# SCH_power_long_clock_2022-06-03.net
KiCad netlist of a schematic drawn in EasyEDA
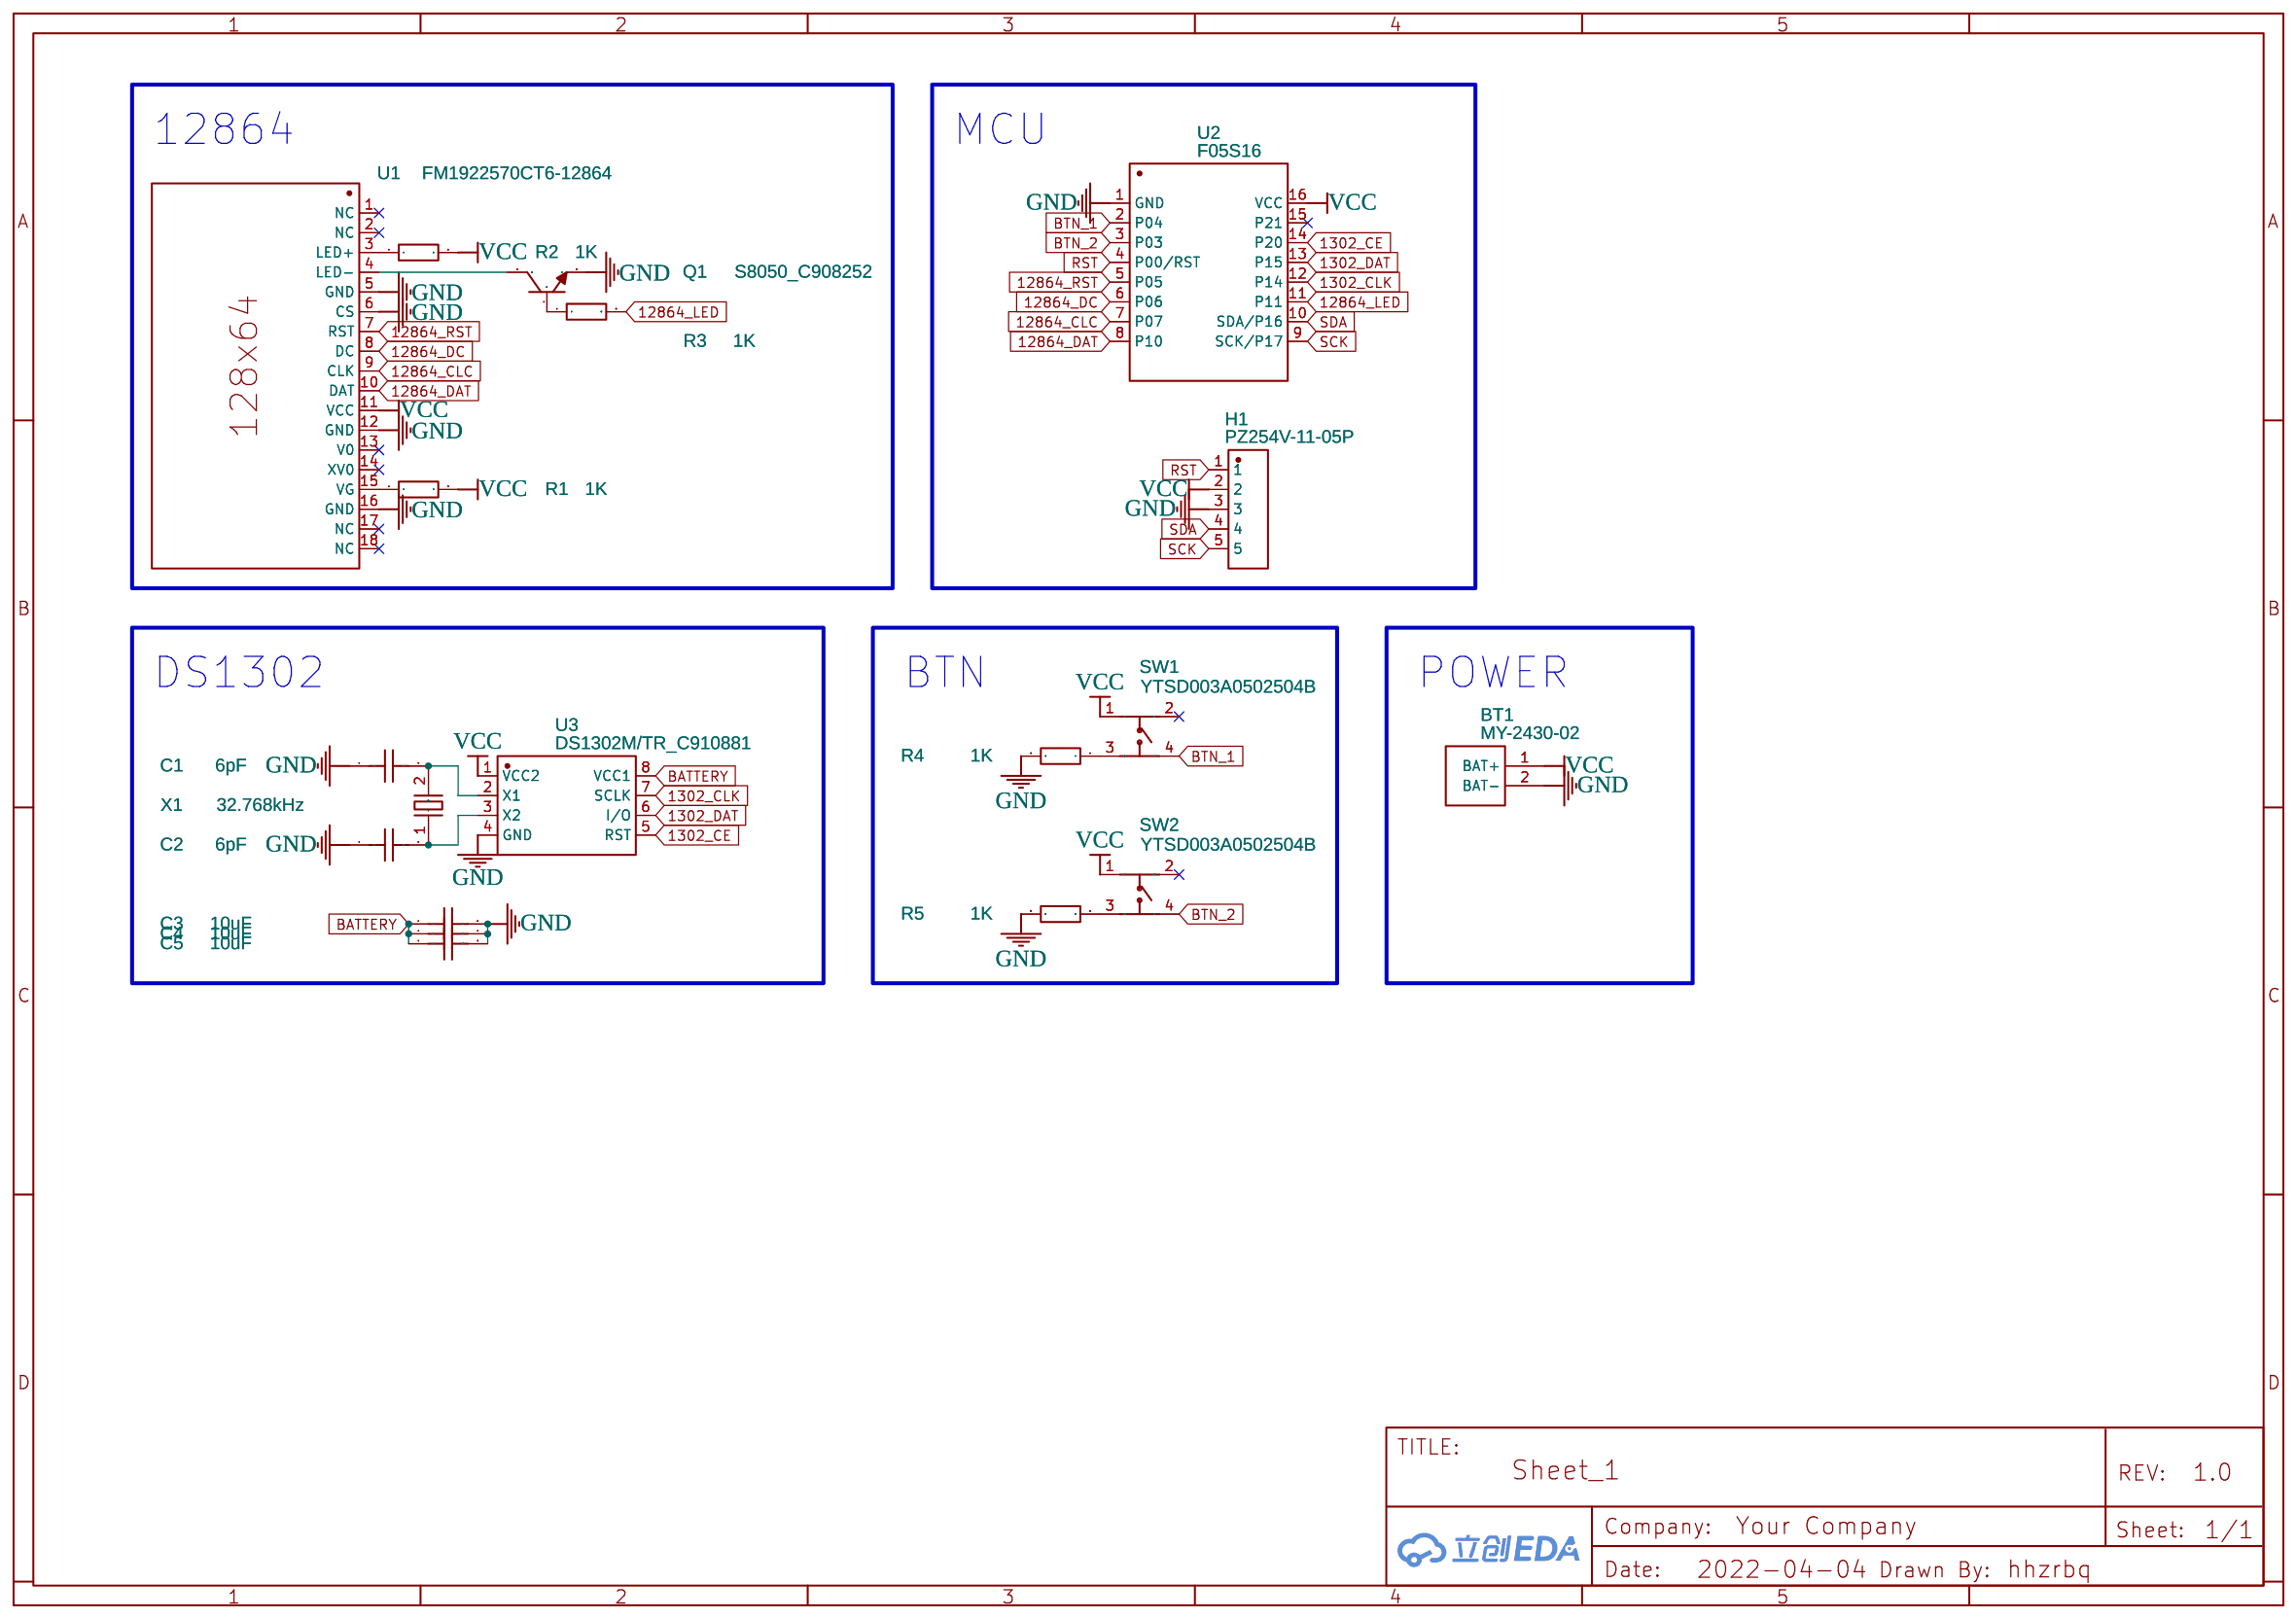
[diagram p0: schematic sheet]

(export (version "E")
  (design (tool "Eeschema 10.0.6"))
  (components
    (comp (ref "BT1")
      (value "MY-2430-02")
      (fields (field (name "BOM_Supplier Part") "C964843"))
      (libsource (lib "") (part "MY-2430-02"))
    )
    (comp (ref "C1")
      (value "6pF")
      (fields
        (field (name "BOM_Manufacturer Part") "0805N6R0D500CT")
        (field (name "BOM_Supplier Part") "C424859")
      )
      (libsource (lib "") (part "0805N6R0D500CT"))
    )
    (comp (ref "C2")
      (value "6pF")
      (fields
        (field (name "BOM_Manufacturer Part") "0805N6R0D500CT")
        (field (name "BOM_Supplier Part") "C424859")
      )
      (libsource (lib "") (part "0805N6R0D500CT"))
    )
    (comp (ref "C3") (value "10uF") (libsource (lib "") (part "C_0805_US")))
    (comp (ref "C4") (value "10uF") (libsource (lib "") (part "C_0805_US")))
    (comp (ref "C5") (value "10uF") (libsource (lib "") (part "C_0805_US")))
    (comp (ref "H1")
      (value "PZ254V-11-05P")
      (fields (field (name "BOM_Supplier Part") "C492404"))
      (libsource (lib "") (part "PZ254V-11-05P"))
    )
    (comp (ref "Q1")
      (value "S8050_C908252")
      (fields (field (name "BOM_Manufacturer Part") "S8050") (field (name "BOM_Supplier Part") "C908252"))
      (libsource (lib "") (part "S8050_C908252"))
    )
    (comp (ref "R1")
      (value "1K")
      (fields
        (field (name "BOM_Manufacturer Part") "RK73B2ATTD102J")
        (field (name "BOM_Supplier Part") "C159911")
      )
      (libsource (lib "") (part "RK73B2ATTD102J_1"))
    )
    (comp (ref "R2")
      (value "1K")
      (fields
        (field (name "BOM_Manufacturer Part") "RK73B2ATTD102J")
        (field (name "BOM_Supplier Part") "C159911")
      )
      (libsource (lib "") (part "RK73B2ATTD102J_1"))
    )
    (comp (ref "R3")
      (value "1K")
      (fields
        (field (name "BOM_Manufacturer Part") "RK73B2ATTD102J")
        (field (name "BOM_Supplier Part") "C159911")
      )
      (libsource (lib "") (part "RK73B2ATTD102J_1"))
    )
    (comp (ref "R4")
      (value "1K")
      (fields
        (field (name "BOM_Manufacturer Part") "RK73B2ATTD102J")
        (field (name "BOM_Supplier Part") "C159911")
      )
      (libsource (lib "") (part "RK73B2ATTD102J"))
    )
    (comp (ref "R5")
      (value "1K")
      (fields
        (field (name "BOM_Manufacturer Part") "RK73B2ATTD102J")
        (field (name "BOM_Supplier Part") "C159911")
      )
      (libsource (lib "") (part "RK73B2ATTD102J"))
    )
    (comp (ref "SW1")
      (value "YTSD003A0502504B")
      (fields (field (name "BOM_Supplier Part") "C2689406"))
      (libsource (lib "") (part "YTSD003A0502504B"))
    )
    (comp (ref "SW2")
      (value "YTSD003A0502504B")
      (fields (field (name "BOM_Supplier Part") "C2689406"))
      (libsource (lib "") (part "YTSD003A0502504B"))
    )
    (comp (ref "U1") (value "FM1922570CT6-12864") (libsource (lib "") (part "FM1922570CT6-12864")))
    (comp (ref "U2") (value "F05S16") (libsource (lib "") (part "F05S16")))
    (comp (ref "U3")
      (value "DS1302M/TR_C910881")
      (fields
        (field (name "BOM_Manufacturer Part") "DS1302M/TR")
        (field (name "BOM_Supplier Part") "C910881")
      )
      (libsource (lib "") (part "DS1302M/TR_C910881"))
    )
    (comp (ref "X1")
      (value "32.768kHz")
      (fields
        (field (name "BOM_Manufacturer Part") "Q13FC13500005")
        (field (name "BOM_Supplier Part") "C841881")
      )
      (libsource (lib "") (part "Q13FC13500005"))
    )
  )
  (nets
    (net (code "1") (name "1302_CE") (class "Default")
      (node (ref "U2") (pin "14") (pinfunction "P20_14") (pintype "bidirectional"))
      (node (ref "U3") (pin "5") (pinfunction "RST_5") (pintype "unspecified"))
    )
    (net (code "2") (name "1302_CLK") (class "Default")
      (node (ref "U2") (pin "12") (pinfunction "P14_12") (pintype "bidirectional"))
      (node (ref "U3") (pin "7") (pinfunction "SCLK_7") (pintype "unspecified"))
    )
    (net (code "3") (name "1302_DAT") (class "Default")
      (node (ref "U2") (pin "13") (pinfunction "P15_13") (pintype "bidirectional"))
      (node (ref "U3") (pin "6") (pinfunction "I/O_6") (pintype "unspecified"))
    )
    (net (code "4") (name "12864_CLC") (class "Default")
      (node (ref "U1") (pin "9") (pinfunction "CLK_9") (pintype "unspecified"))
      (node (ref "U2") (pin "7") (pinfunction "P07_7") (pintype "bidirectional"))
    )
    (net (code "5") (name "12864_DAT") (class "Default")
      (node (ref "U1") (pin "10") (pinfunction "DAT_10") (pintype "unspecified"))
      (node (ref "U2") (pin "8") (pinfunction "P10_8") (pintype "bidirectional"))
    )
    (net (code "6") (name "12864_DC") (class "Default")
      (node (ref "U1") (pin "8") (pinfunction "DC_8") (pintype "unspecified"))
      (node (ref "U2") (pin "6") (pinfunction "P06_6") (pintype "bidirectional"))
    )
    (net (code "7") (name "12864_LED") (class "Default")
      (node (ref "R3") (pin "2") (pinfunction "2_2") (pintype "unspecified"))
      (node (ref "U2") (pin "11") (pinfunction "P11_11") (pintype "bidirectional"))
    )
    (net (code "8") (name "12864_RST") (class "Default")
      (node (ref "U1") (pin "7") (pinfunction "RST_7") (pintype "unspecified"))
      (node (ref "U2") (pin "5") (pinfunction "P05_5") (pintype "bidirectional"))
    )
    (net (code "9") (name "BATTERY") (class "Default")
      (node (ref "C3") (pin "1") (pinfunction "1_1") (pintype "unspecified"))
      (node (ref "C4") (pin "1") (pinfunction "1_1") (pintype "unspecified"))
      (node (ref "C5") (pin "1") (pinfunction "1_1") (pintype "unspecified"))
      (node (ref "U3") (pin "8") (pinfunction "VCC1_8") (pintype "unspecified"))
    )
    (net (code "10") (name "BTN_1") (class "Default")
      (node (ref "SW1") (pin "4") (pinfunction "4_4") (pintype "unspecified"))
      (node (ref "U2") (pin "2") (pinfunction "P04_2") (pintype "bidirectional"))
    )
    (net (code "11") (name "BTN_2") (class "Default")
      (node (ref "SW2") (pin "4") (pinfunction "4_4") (pintype "unspecified"))
      (node (ref "U2") (pin "3") (pinfunction "P03_3") (pintype "bidirectional"))
    )
    (net (code "12") (name "GND") (class "Default")
      (node (ref "BT1") (pin "2") (pinfunction "BAT-_2") (pintype "unspecified"))
      (node (ref "C1") (pin "1") (pinfunction "1_1") (pintype "unspecified"))
      (node (ref "C2") (pin "1") (pinfunction "1_1") (pintype "unspecified"))
      (node (ref "C3") (pin "2") (pinfunction "2_2") (pintype "unspecified"))
      (node (ref "C4") (pin "2") (pinfunction "2_2") (pintype "unspecified"))
      (node (ref "C5") (pin "2") (pinfunction "2_2") (pintype "unspecified"))
      (node (ref "H1") (pin "3") (pinfunction "3_3") (pintype "unspecified"))
      (node (ref "Q1") (pin "2") (pinfunction "E_2") (pintype "input"))
      (node (ref "R4") (pin "2") (pinfunction "2_2") (pintype "unspecified"))
      (node (ref "R5") (pin "2") (pinfunction "2_2") (pintype "unspecified"))
      (node (ref "U1") (pin "12") (pinfunction "GND_12") (pintype "unspecified"))
      (node (ref "U1") (pin "16") (pinfunction "GND_16") (pintype "unspecified"))
      (node (ref "U1") (pin "5") (pinfunction "GND_5") (pintype "unspecified"))
      (node (ref "U1") (pin "6") (pinfunction "CS_6") (pintype "unspecified"))
      (node (ref "U2") (pin "1") (pinfunction "GND_1") (pintype "passive"))
      (node (ref "U3") (pin "4") (pinfunction "GND_4") (pintype "unspecified"))
    )
    (net (code "13") (name "Net-(Q1-B)") (class "Default")
      (node (ref "Q1") (pin "1") (pinfunction "B_1") (pintype "input"))
      (node (ref "R3") (pin "1") (pinfunction "1_1") (pintype "unspecified"))
    )
    (net (code "14") (name "Net-(Q1-C)") (class "Default")
      (node (ref "Q1") (pin "3") (pinfunction "C_3") (pintype "input"))
      (node (ref "U1") (pin "4") (pinfunction "LED-_4") (pintype "unspecified"))
    )
    (net (code "15") (name "Net-(R4-Pad1)") (class "Default")
      (node (ref "R4") (pin "1") (pinfunction "1_1") (pintype "unspecified"))
      (node (ref "SW1") (pin "3") (pinfunction "3_3") (pintype "unspecified"))
    )
    (net (code "16") (name "Net-(R5-Pad1)") (class "Default")
      (node (ref "R5") (pin "1") (pinfunction "1_1") (pintype "unspecified"))
      (node (ref "SW2") (pin "3") (pinfunction "3_3") (pintype "unspecified"))
    )
    (net (code "17") (name "Net-(U1-LED+)") (class "Default")
      (node (ref "R2") (pin "1") (pinfunction "1_1") (pintype "unspecified"))
      (node (ref "U1") (pin "3") (pinfunction "LED+_3") (pintype "unspecified"))
    )
    (net (code "18") (name "Net-(U1-VG)") (class "Default")
      (node (ref "R1") (pin "1") (pinfunction "1_1") (pintype "unspecified"))
      (node (ref "U1") (pin "15") (pinfunction "VG_15") (pintype "unspecified"))
    )
    (net (code "19") (name "Net-(U3-X1)") (class "Default")
      (node (ref "C1") (pin "2") (pinfunction "2_2") (pintype "unspecified"))
      (node (ref "U3") (pin "2") (pinfunction "X1_2") (pintype "unspecified"))
      (node (ref "X1") (pin "2") (pinfunction "GND_2") (pintype "input"))
    )
    (net (code "20") (name "Net-(U3-X2)") (class "Default")
      (node (ref "C2") (pin "2") (pinfunction "2_2") (pintype "unspecified"))
      (node (ref "U3") (pin "3") (pinfunction "X2_3") (pintype "unspecified"))
      (node (ref "X1") (pin "1") (pinfunction "1_1") (pintype "input"))
    )
    (net (code "21") (name "RST") (class "Default")
      (node (ref "H1") (pin "1") (pinfunction "1_1") (pintype "unspecified"))
      (node (ref "U2") (pin "4") (pinfunction "P00/RST_4") (pintype "bidirectional"))
    )
    (net (code "22") (name "SCK") (class "Default")
      (node (ref "H1") (pin "5") (pinfunction "5_5") (pintype "unspecified"))
      (node (ref "U2") (pin "9") (pinfunction "SCK/P17_9") (pintype "bidirectional"))
    )
    (net (code "23") (name "SDA") (class "Default")
      (node (ref "H1") (pin "4") (pinfunction "4_4") (pintype "unspecified"))
      (node (ref "U2") (pin "10") (pinfunction "SDA/P16_10") (pintype "bidirectional"))
    )
    (net (code "24") (name "VCC") (class "Default")
      (node (ref "BT1") (pin "1") (pinfunction "BAT+_1") (pintype "unspecified"))
      (node (ref "H1") (pin "2") (pinfunction "2_2") (pintype "unspecified"))
      (node (ref "R1") (pin "2") (pinfunction "2_2") (pintype "unspecified"))
      (node (ref "R2") (pin "2") (pinfunction "2_2") (pintype "unspecified"))
      (node (ref "SW1") (pin "1") (pinfunction "1_1") (pintype "unspecified"))
      (node (ref "SW2") (pin "1") (pinfunction "1_1") (pintype "unspecified"))
      (node (ref "U1") (pin "11") (pinfunction "VCC_11") (pintype "unspecified"))
      (node (ref "U2") (pin "16") (pinfunction "VCC_16") (pintype "passive"))
      (node (ref "U3") (pin "1") (pinfunction "VCC2_1") (pintype "unspecified"))
    )
    (net (code "25") (name "unconnected-(SW1-Pad2)") (class "Default")
      (node (ref "SW1") (pin "2") (pinfunction "2_2") (pintype "unspecified+no_connect"))
    )
    (net (code "26") (name "unconnected-(SW2-Pad2)") (class "Default")
      (node (ref "SW2") (pin "2") (pinfunction "2_2") (pintype "unspecified+no_connect"))
    )
    (net (code "27") (name "unconnected-(U1-NC-Pad1)") (class "Default")
      (node (ref "U1") (pin "1") (pinfunction "NC_1") (pintype "unspecified+no_connect"))
    )
    (net (code "28") (name "unconnected-(U1-NC-Pad2)") (class "Default")
      (node (ref "U1") (pin "2") (pinfunction "NC_2") (pintype "unspecified+no_connect"))
    )
    (net (code "29") (name "unconnected-(U1-NC-Pad17)") (class "Default")
      (node (ref "U1") (pin "17") (pinfunction "NC_17") (pintype "unspecified+no_connect"))
    )
    (net (code "30") (name "unconnected-(U1-NC-Pad18)") (class "Default")
      (node (ref "U1") (pin "18") (pinfunction "NC_18") (pintype "unspecified+no_connect"))
    )
    (net (code "31") (name "unconnected-(U1-V0-Pad13)") (class "Default")
      (node (ref "U1") (pin "13") (pinfunction "V0_13") (pintype "unspecified+no_connect"))
    )
    (net (code "32") (name "unconnected-(U1-XV0-Pad14)") (class "Default")
      (node (ref "U1") (pin "14") (pinfunction "XV0_14") (pintype "unspecified+no_connect"))
    )
    (net (code "33") (name "unconnected-(U2-P21-Pad15)") (class "Default")
      (node (ref "U2") (pin "15") (pinfunction "P21_15") (pintype "bidirectional+no_connect"))
    )
  )
)
